# 05_IO.net
KiCad netlist of a schematic drawn in Altium Designer
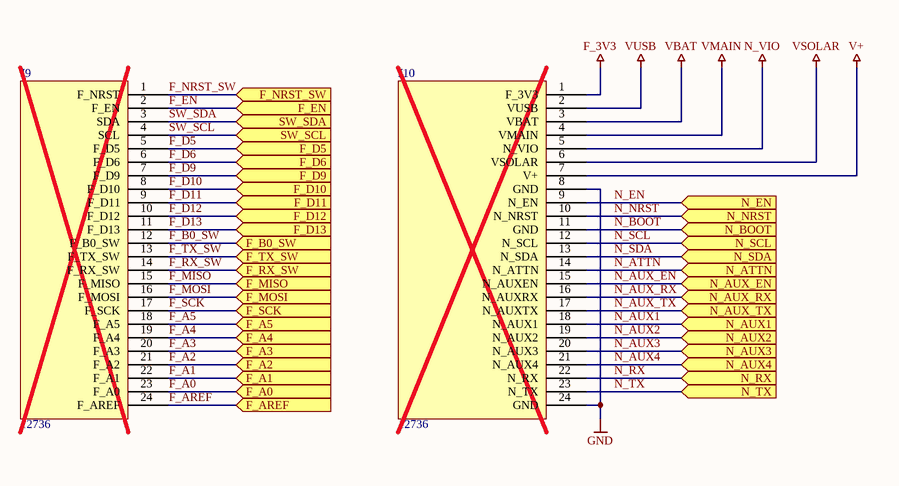
[diagram p0: 05_IO.SchDoc]

(export (version "E")
  (design (tool "Eeschema 10.0.6"))
  (components
    (comp (ref "J9")
      (value "12736")
      (footprint "CES-124-01-S-S")
      (description "24x1 0.1\" pitch half height female header")
      (fields
        (field (name "MANUFACTURER") "4UCON")
        (field (name "BL PART NUMBER") "2010-425")
        (field (name "DRAWN_BY") "Blues Wireless")
      )
      (libsource (lib "n21-p2") (part "SIDECON"))
    )
    (comp (ref "J10")
      (value "12736")
      (footprint "CES-124-01-S-S")
      (description "24x1 0.1\" pitch half height female header")
      (fields
        (field (name "MANUFACTURER") "4UCON")
        (field (name "BL PART NUMBER") "2010-425")
        (field (name "DRAWN_BY") "Blues Wireless")
      )
      (libsource (lib "n21-p2") (part "SIDECON_N"))
    )
  )
  (nets
    (net (code "1") (name "/F_A0") (class "Default")
      (node (ref "J9") (pin "23") (pinfunction "F_A0_23") (pintype "passive"))
    )
    (net (code "2") (name "/F_A1") (class "Default")
      (node (ref "J9") (pin "22") (pinfunction "F_A1_22") (pintype "passive"))
    )
    (net (code "3") (name "/F_A2") (class "Default")
      (node (ref "J9") (pin "21") (pinfunction "F_A2_21") (pintype "passive"))
    )
    (net (code "4") (name "/F_A3") (class "Default")
      (node (ref "J9") (pin "20") (pinfunction "F_A3_20") (pintype "passive"))
    )
    (net (code "5") (name "/F_A4") (class "Default")
      (node (ref "J9") (pin "19") (pinfunction "F_A4_19") (pintype "passive"))
    )
    (net (code "6") (name "/F_A5") (class "Default")
      (node (ref "J9") (pin "18") (pinfunction "F_A5_18") (pintype "passive"))
    )
    (net (code "7") (name "/F_AREF") (class "Default")
      (node (ref "J9") (pin "24") (pinfunction "F_AREF_24") (pintype "passive"))
    )
    (net (code "8") (name "/F_B0_SW") (class "Default")
      (node (ref "J9") (pin "12") (pinfunction "F_B0_SW_12") (pintype "passive"))
    )
    (net (code "9") (name "/F_D5") (class "Default")
      (node (ref "J9") (pin "5") (pinfunction "F_D5_5") (pintype "passive"))
    )
    (net (code "10") (name "/F_D6") (class "Default")
      (node (ref "J9") (pin "6") (pinfunction "F_D6_6") (pintype "passive"))
    )
    (net (code "11") (name "/F_D9") (class "Default")
      (node (ref "J9") (pin "7") (pinfunction "F_D9_7") (pintype "passive"))
    )
    (net (code "12") (name "/F_D10") (class "Default")
      (node (ref "J9") (pin "8") (pinfunction "F_D10_8") (pintype "passive"))
    )
    (net (code "13") (name "/F_D11") (class "Default")
      (node (ref "J9") (pin "9") (pinfunction "F_D11_9") (pintype "passive"))
    )
    (net (code "14") (name "/F_D12") (class "Default")
      (node (ref "J9") (pin "10") (pinfunction "F_D12_10") (pintype "passive"))
    )
    (net (code "15") (name "/F_D13") (class "Default")
      (node (ref "J9") (pin "11") (pinfunction "F_D13_11") (pintype "passive"))
    )
    (net (code "16") (name "/F_EN") (class "Default")
      (node (ref "J9") (pin "2") (pinfunction "F_EN_2") (pintype "passive"))
    )
    (net (code "17") (name "/F_MISO") (class "Default")
      (node (ref "J9") (pin "15") (pinfunction "F_MISO_15") (pintype "passive"))
    )
    (net (code "18") (name "/F_MOSI") (class "Default")
      (node (ref "J9") (pin "16") (pinfunction "F_MOSI_16") (pintype "passive"))
    )
    (net (code "19") (name "/F_NRST_SW") (class "Default")
      (node (ref "J9") (pin "1") (pinfunction "F_NRST_1") (pintype "passive"))
    )
    (net (code "20") (name "/F_RX_SW") (class "Default")
      (node (ref "J9") (pin "14") (pinfunction "F_RX_SW_14") (pintype "passive"))
    )
    (net (code "21") (name "/F_SCK") (class "Default")
      (node (ref "J9") (pin "17") (pinfunction "F_SCK_17") (pintype "passive"))
    )
    (net (code "22") (name "/F_TX_SW") (class "Default")
      (node (ref "J9") (pin "13") (pinfunction "F_TX_SW_13") (pintype "passive"))
    )
    (net (code "23") (name "/N_ATTN") (class "Default")
      (node (ref "J10") (pin "14") (pinfunction "N_ATTN_14") (pintype "passive"))
    )
    (net (code "24") (name "/N_AUX1") (class "Default")
      (node (ref "J10") (pin "18") (pinfunction "N_AUX1_18") (pintype "passive"))
    )
    (net (code "25") (name "/N_AUX2") (class "Default")
      (node (ref "J10") (pin "19") (pinfunction "N_AUX2_19") (pintype "passive"))
    )
    (net (code "26") (name "/N_AUX3") (class "Default")
      (node (ref "J10") (pin "20") (pinfunction "N_AUX3_20") (pintype "passive"))
    )
    (net (code "27") (name "/N_AUX4") (class "Default")
      (node (ref "J10") (pin "21") (pinfunction "N_AUX4_21") (pintype "passive"))
    )
    (net (code "28") (name "/N_AUX_EN") (class "Default")
      (node (ref "J10") (pin "15") (pinfunction "N_AUXEN_15") (pintype "passive"))
    )
    (net (code "29") (name "/N_AUX_RX") (class "Default")
      (node (ref "J10") (pin "16") (pinfunction "N_AUXRX_16") (pintype "passive"))
    )
    (net (code "30") (name "/N_AUX_TX") (class "Default")
      (node (ref "J10") (pin "17") (pinfunction "N_AUXTX_17") (pintype "passive"))
    )
    (net (code "31") (name "/N_BOOT") (class "Default")
      (node (ref "J10") (pin "11") (pinfunction "GND_11") (pintype "passive"))
    )
    (net (code "32") (name "/N_EN") (class "Default")
      (node (ref "J10") (pin "9") (pinfunction "N_EN_9") (pintype "passive"))
    )
    (net (code "33") (name "/N_NRST") (class "Default")
      (node (ref "J10") (pin "10") (pinfunction "N_NRST_10") (pintype "passive"))
    )
    (net (code "34") (name "/N_RX") (class "Default")
      (node (ref "J10") (pin "22") (pinfunction "N_RX_22") (pintype "passive"))
    )
    (net (code "35") (name "/N_SCL") (class "Default")
      (node (ref "J10") (pin "12") (pinfunction "N_SCL_12") (pintype "passive"))
    )
    (net (code "36") (name "/N_SDA") (class "Default")
      (node (ref "J10") (pin "13") (pinfunction "N_SDA_13") (pintype "passive"))
    )
    (net (code "37") (name "/N_TX") (class "Default")
      (node (ref "J10") (pin "23") (pinfunction "N_TX_23") (pintype "passive"))
    )
    (net (code "38") (name "/SW_SCL") (class "Default")
      (node (ref "J9") (pin "4") (pinfunction "SCL_4") (pintype "passive"))
    )
    (net (code "39") (name "/SW_SDA") (class "Default")
      (node (ref "J9") (pin "3") (pinfunction "SDA_3") (pintype "passive"))
    )
    (net (code "40") (name "F_3V3") (class "Default")
      (node (ref "J10") (pin "1") (pinfunction "F_3V3_1") (pintype "passive"))
    )
    (net (code "41") (name "GND") (class "Default")
      (node (ref "J10") (pin "24") (pinfunction "GND_24") (pintype "passive"))
      (node (ref "J10") (pin "8") (pinfunction "GND_8") (pintype "passive"))
    )
    (net (code "42") (name "N_VIO") (class "Default")
      (node (ref "J10") (pin "5") (pinfunction "N_VIO_5") (pintype "passive"))
    )
    (net (code "43") (name "V+") (class "Default")
      (node (ref "J10") (pin "7") (pinfunction "V+_7") (pintype "passive"))
    )
    (net (code "44") (name "VBAT") (class "Default")
      (node (ref "J10") (pin "3") (pinfunction "VBAT_3") (pintype "passive"))
    )
    (net (code "45") (name "VMAIN") (class "Default")
      (node (ref "J10") (pin "4") (pinfunction "VMAIN_4") (pintype "passive"))
    )
    (net (code "46") (name "VSOLAR") (class "Default")
      (node (ref "J10") (pin "6") (pinfunction "VSOLAR_6") (pintype "passive"))
    )
    (net (code "47") (name "VUSB") (class "Default")
      (node (ref "J10") (pin "2") (pinfunction "VUSB_2") (pintype "passive"))
    )
  )
)
